# n64_4_port.net
KiCad netlist of a schematic drawn in EAGLE
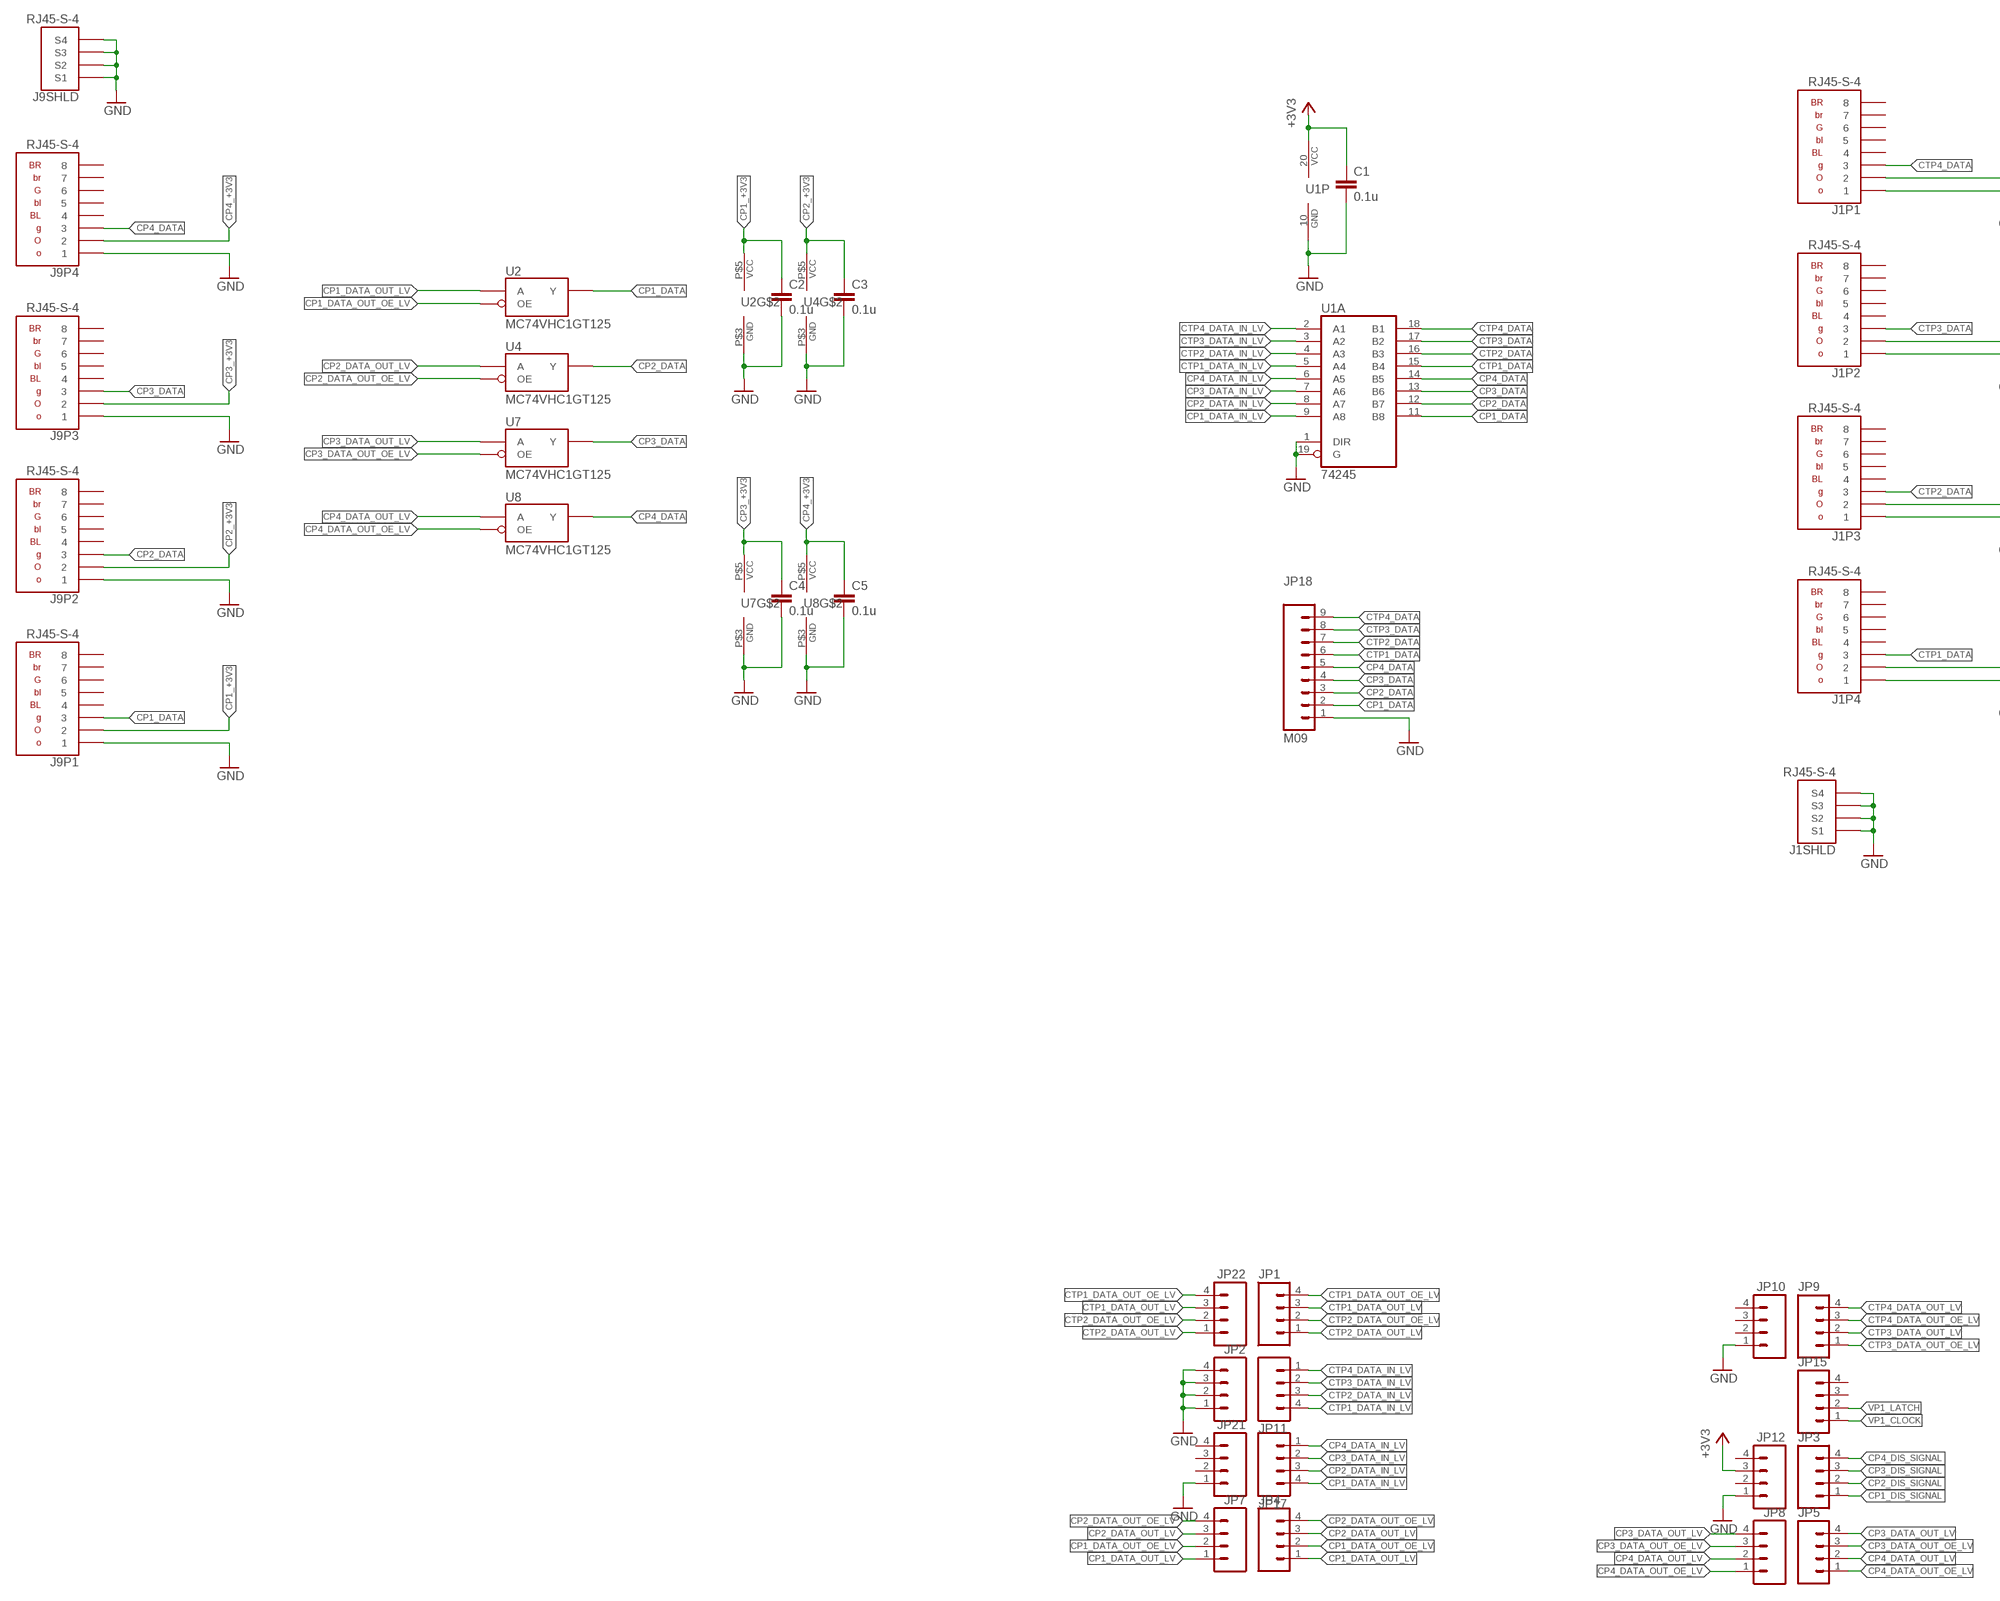
[diagram p0: schematic, sheet 1, part 1 of 2]
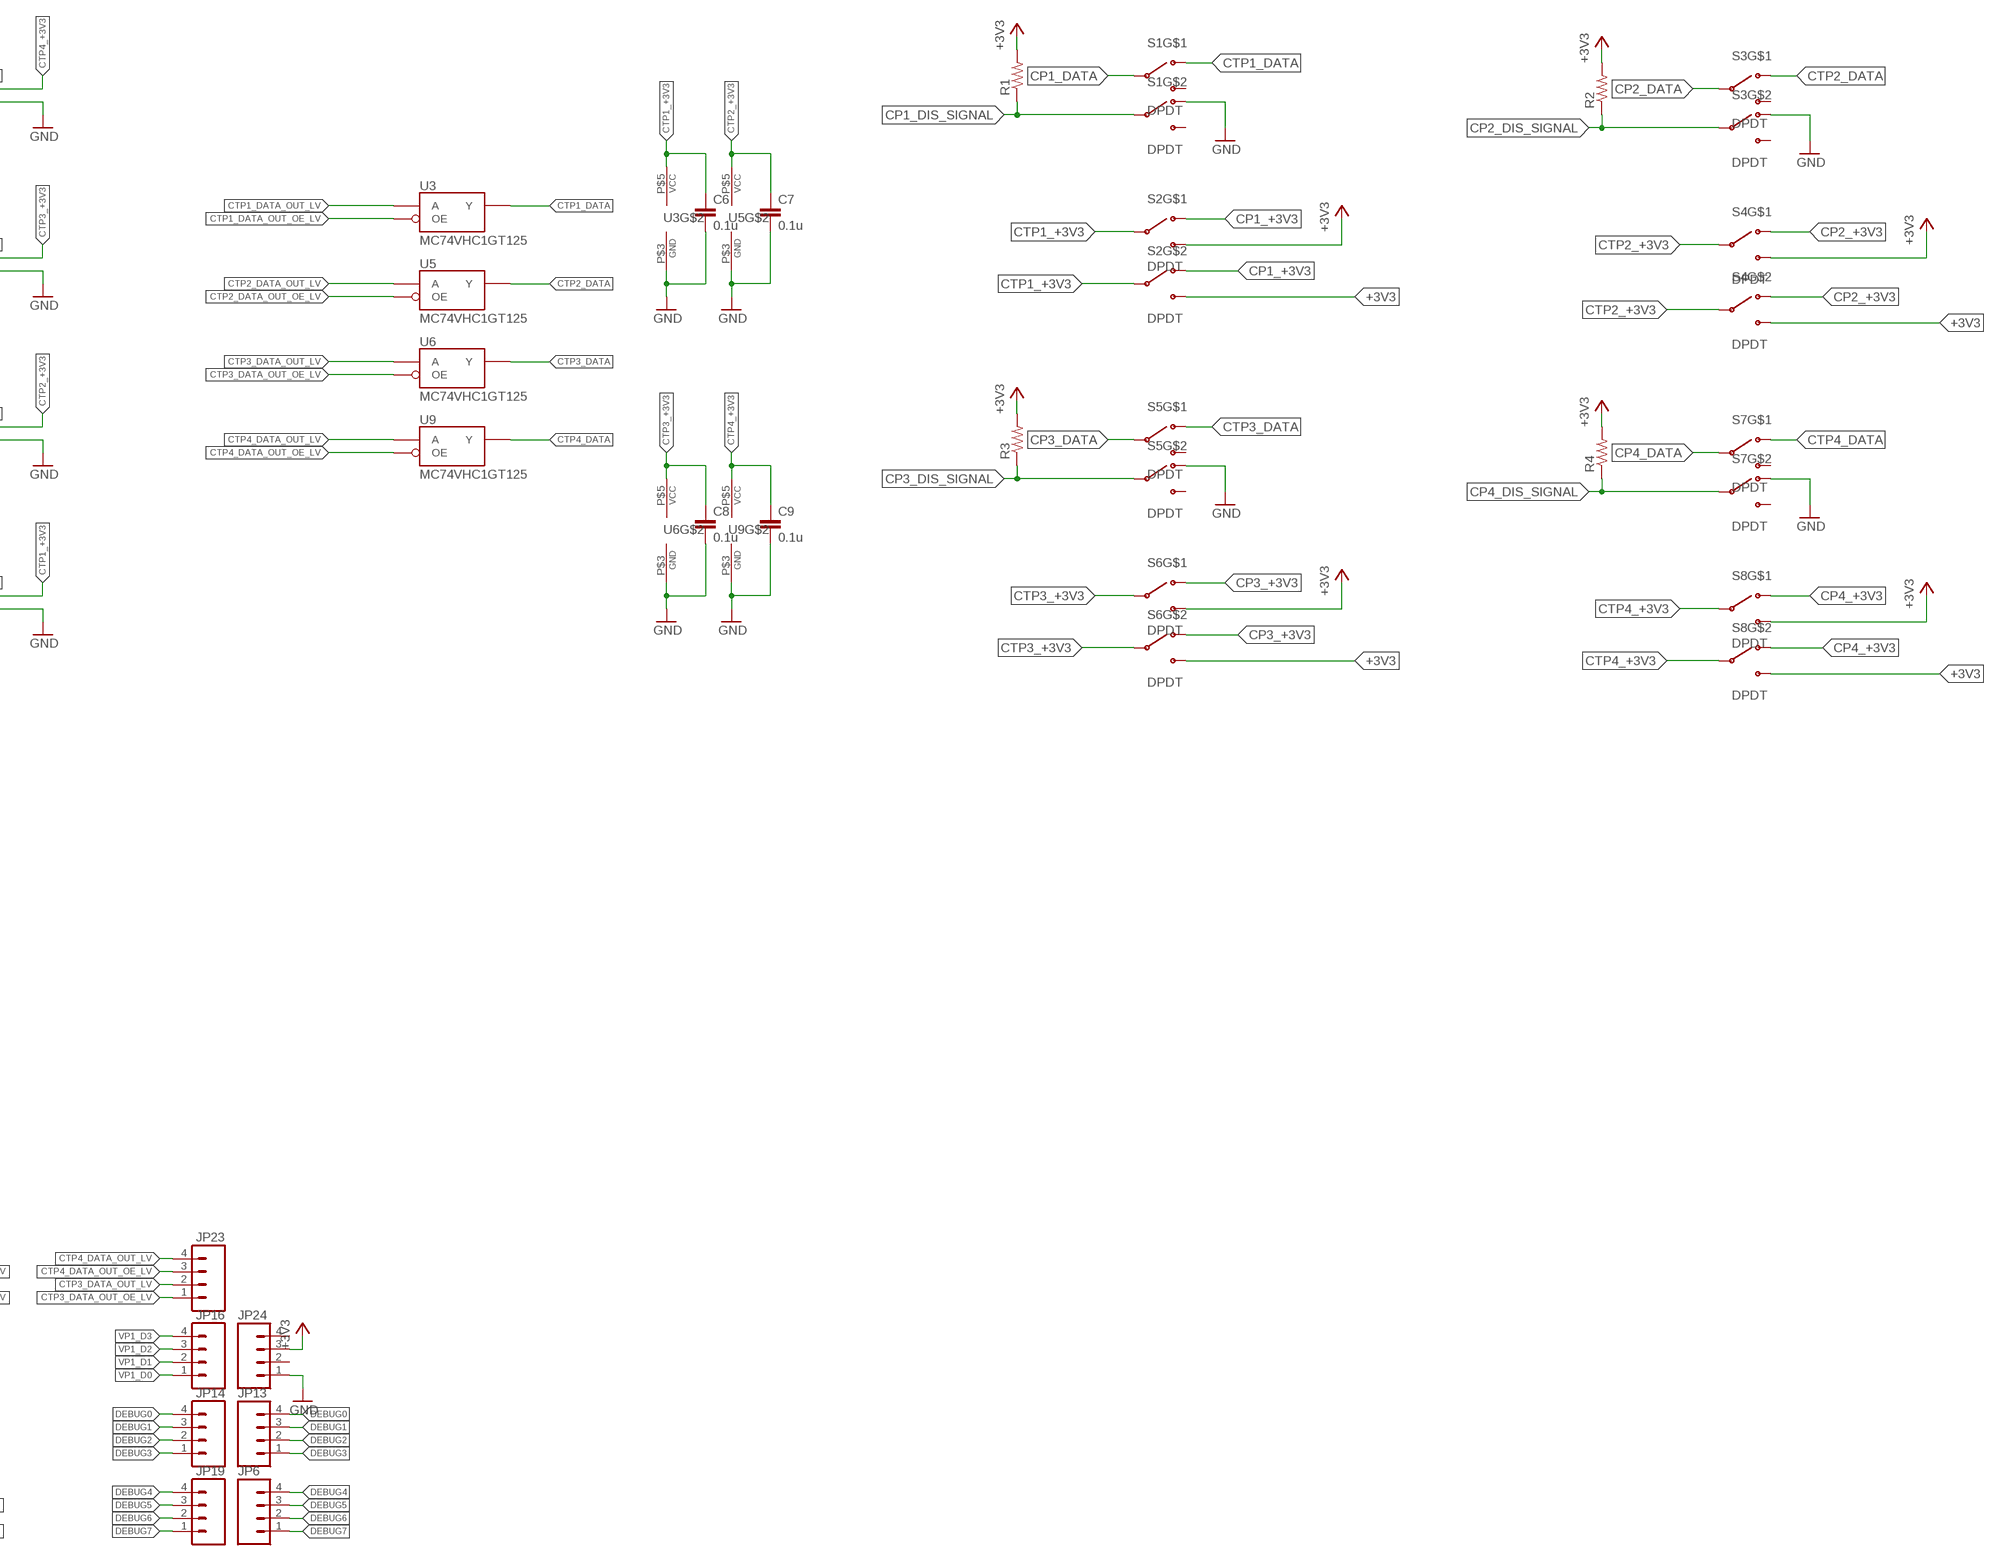
[diagram p1: schematic, sheet 1, part 2 of 2]

(export (version "E")
  (design (tool "Eeschema 10.0.6"))
  (components
    (comp (ref "C1")
      (value "0.1u")
      (footprint "eagle-import:C0603")
      (libsource (lib "eagle-import") (part "C-EUC0603"))
    )
    (comp (ref "C2")
      (value "0.1u")
      (footprint "eagle-import:C0603")
      (libsource (lib "eagle-import") (part "C-EUC0603"))
    )
    (comp (ref "C3")
      (value "0.1u")
      (footprint "eagle-import:C0603")
      (libsource (lib "eagle-import") (part "C-EUC0603"))
    )
    (comp (ref "C4")
      (value "0.1u")
      (footprint "eagle-import:C0603")
      (libsource (lib "eagle-import") (part "C-EUC0603"))
    )
    (comp (ref "C5")
      (value "0.1u")
      (footprint "eagle-import:C0603")
      (libsource (lib "eagle-import") (part "C-EUC0603"))
    )
    (comp (ref "C6")
      (value "0.1u")
      (footprint "eagle-import:C0603")
      (libsource (lib "eagle-import") (part "C-EUC0603"))
    )
    (comp (ref "C7")
      (value "0.1u")
      (footprint "eagle-import:C0603")
      (libsource (lib "eagle-import") (part "C-EUC0603"))
    )
    (comp (ref "C8")
      (value "0.1u")
      (footprint "eagle-import:C0603")
      (libsource (lib "eagle-import") (part "C-EUC0603"))
    )
    (comp (ref "C9")
      (value "0.1u")
      (footprint "eagle-import:C0603")
      (libsource (lib "eagle-import") (part "C-EUC0603"))
    )
    (comp (ref "J1")
      (value "RJ45-S-4")
      (footprint "eagle-import:RJ45-S-4")
      (libsource (lib "eagle-import") (part "RJ45-S-4"))
    )
    (comp (ref "J9")
      (value "RJ45-S-4")
      (footprint "eagle-import:RJ45-S-4")
      (libsource (lib "eagle-import") (part "RJ45-S-4"))
    )
    (comp (ref "JP1")
      (value "M04PTH")
      (footprint "eagle-import:1X04")
      (libsource (lib "eagle-import") (part "M04PTH"))
    )
    (comp (ref "JP2")
      (value "M04PTH")
      (footprint "eagle-import:1X04")
      (libsource (lib "eagle-import") (part "M04PTH"))
    )
    (comp (ref "JP3")
      (value "M04PTH")
      (footprint "eagle-import:1X04")
      (libsource (lib "eagle-import") (part "M04PTH"))
    )
    (comp (ref "JP4")
      (value "M04PTH")
      (footprint "eagle-import:1X04")
      (libsource (lib "eagle-import") (part "M04PTH"))
    )
    (comp (ref "JP5")
      (value "M04PTH")
      (footprint "eagle-import:1X04")
      (libsource (lib "eagle-import") (part "M04PTH"))
    )
    (comp (ref "JP6")
      (value "M04PTH")
      (footprint "eagle-import:1X04")
      (libsource (lib "eagle-import") (part "M04PTH"))
    )
    (comp (ref "JP7")
      (value "M04PTH")
      (footprint "eagle-import:1X04")
      (libsource (lib "eagle-import") (part "M04PTH"))
    )
    (comp (ref "JP8")
      (value "M04PTH")
      (footprint "eagle-import:1X04")
      (libsource (lib "eagle-import") (part "M04PTH"))
    )
    (comp (ref "JP9")
      (value "M04PTH")
      (footprint "eagle-import:1X04")
      (libsource (lib "eagle-import") (part "M04PTH"))
    )
    (comp (ref "JP10")
      (value "M04PTH")
      (footprint "eagle-import:1X04")
      (libsource (lib "eagle-import") (part "M04PTH"))
    )
    (comp (ref "JP11")
      (value "M04PTH")
      (footprint "eagle-import:1X04")
      (libsource (lib "eagle-import") (part "M04PTH"))
    )
    (comp (ref "JP12")
      (value "M04PTH")
      (footprint "eagle-import:1X04")
      (libsource (lib "eagle-import") (part "M04PTH"))
    )
    (comp (ref "JP13")
      (value "M04PTH")
      (footprint "eagle-import:1X04")
      (libsource (lib "eagle-import") (part "M04PTH"))
    )
    (comp (ref "JP14")
      (value "M04PTH")
      (footprint "eagle-import:1X04")
      (libsource (lib "eagle-import") (part "M04PTH"))
    )
    (comp (ref "JP15")
      (value "M04PTH")
      (footprint "eagle-import:1X04")
      (libsource (lib "eagle-import") (part "M04PTH"))
    )
    (comp (ref "JP16")
      (value "M04PTH")
      (footprint "eagle-import:1X04")
      (libsource (lib "eagle-import") (part "M04PTH"))
    )
    (comp (ref "JP17")
      (value "M04PTH")
      (footprint "eagle-import:1X04")
      (libsource (lib "eagle-import") (part "M04PTH"))
    )
    (comp (ref "JP18")
      (value "M09")
      (footprint "eagle-import:1X09")
      (libsource (lib "eagle-import") (part "M09"))
    )
    (comp (ref "JP19")
      (value "M04PTH")
      (footprint "eagle-import:1X04")
      (libsource (lib "eagle-import") (part "M04PTH"))
    )
    (comp (ref "JP21")
      (value "M04PTH")
      (footprint "eagle-import:1X04")
      (libsource (lib "eagle-import") (part "M04PTH"))
    )
    (comp (ref "JP22")
      (value "M04PTH")
      (footprint "eagle-import:1X04")
      (libsource (lib "eagle-import") (part "M04PTH"))
    )
    (comp (ref "JP23")
      (value "M04PTH")
      (footprint "eagle-import:1X04")
      (libsource (lib "eagle-import") (part "M04PTH"))
    )
    (comp (ref "JP24")
      (value "M04PTH")
      (footprint "eagle-import:1X04")
      (libsource (lib "eagle-import") (part "M04PTH"))
    )
    (comp (ref "R1")
      (value "R-US_0207/2V")
      (footprint "eagle-import:0207_2V")
      (libsource (lib "eagle-import") (part "R-US_0207/2V"))
    )
    (comp (ref "R2")
      (value "R-US_0207/2V")
      (footprint "eagle-import:0207_2V")
      (libsource (lib "eagle-import") (part "R-US_0207/2V"))
    )
    (comp (ref "R3")
      (value "R-US_0207/2V")
      (footprint "eagle-import:0207_2V")
      (libsource (lib "eagle-import") (part "R-US_0207/2V"))
    )
    (comp (ref "R4")
      (value "R-US_0207/2V")
      (footprint "eagle-import:0207_2V")
      (libsource (lib "eagle-import") (part "R-US_0207/2V"))
    )
    (comp (ref "S1")
      (value "DPDT")
      (footprint "eagle-import:JS202011CQN")
      (libsource (lib "eagle-import") (part "DPDT"))
    )
    (comp (ref "S2")
      (value "DPDT")
      (footprint "eagle-import:JS202011CQN")
      (libsource (lib "eagle-import") (part "DPDT"))
    )
    (comp (ref "S3")
      (value "DPDT")
      (footprint "eagle-import:JS202011CQN")
      (libsource (lib "eagle-import") (part "DPDT"))
    )
    (comp (ref "S4")
      (value "DPDT")
      (footprint "eagle-import:JS202011CQN")
      (libsource (lib "eagle-import") (part "DPDT"))
    )
    (comp (ref "S5")
      (value "DPDT")
      (footprint "eagle-import:JS202011CQN")
      (libsource (lib "eagle-import") (part "DPDT"))
    )
    (comp (ref "S6")
      (value "DPDT")
      (footprint "eagle-import:JS202011CQN")
      (libsource (lib "eagle-import") (part "DPDT"))
    )
    (comp (ref "S7")
      (value "DPDT")
      (footprint "eagle-import:JS202011CQN")
      (libsource (lib "eagle-import") (part "DPDT"))
    )
    (comp (ref "S8")
      (value "DPDT")
      (footprint "eagle-import:JS202011CQN")
      (libsource (lib "eagle-import") (part "DPDT"))
    )
    (comp (ref "U1")
      (value "74245")
      (footprint "eagle-import:DIL20")
      (libsource (lib "eagle-import") (part "74245"))
    )
    (comp (ref "U2")
      (value "MC74VHC1GT125")
      (footprint "eagle-import:TSOP-5")
      (libsource (lib "eagle-import") (part "MC74VHC1GT125"))
    )
    (comp (ref "U3")
      (value "MC74VHC1GT125")
      (footprint "eagle-import:TSOP-5")
      (libsource (lib "eagle-import") (part "MC74VHC1GT125"))
    )
    (comp (ref "U4")
      (value "MC74VHC1GT125")
      (footprint "eagle-import:TSOP-5")
      (libsource (lib "eagle-import") (part "MC74VHC1GT125"))
    )
    (comp (ref "U5")
      (value "MC74VHC1GT125")
      (footprint "eagle-import:TSOP-5")
      (libsource (lib "eagle-import") (part "MC74VHC1GT125"))
    )
    (comp (ref "U6")
      (value "MC74VHC1GT125")
      (footprint "eagle-import:TSOP-5")
      (libsource (lib "eagle-import") (part "MC74VHC1GT125"))
    )
    (comp (ref "U7")
      (value "MC74VHC1GT125")
      (footprint "eagle-import:TSOP-5")
      (libsource (lib "eagle-import") (part "MC74VHC1GT125"))
    )
    (comp (ref "U8")
      (value "MC74VHC1GT125")
      (footprint "eagle-import:TSOP-5")
      (libsource (lib "eagle-import") (part "MC74VHC1GT125"))
    )
    (comp (ref "U9")
      (value "MC74VHC1GT125")
      (footprint "eagle-import:TSOP-5")
      (libsource (lib "eagle-import") (part "MC74VHC1GT125"))
    )
  )
  (nets
    (net (code "1") (name "+3V3") (class "Default")
      (node (ref "C1") (pin "1") (pinfunction "1_1") (pintype "passive"))
      (node (ref "JP12") (pin "3") (pinfunction "3_3") (pintype "passive"))
      (node (ref "JP24") (pin "3") (pinfunction "3_3") (pintype "passive"))
      (node (ref "R1") (pin "2") (pinfunction "2_2") (pintype "passive"))
      (node (ref "R2") (pin "2") (pinfunction "2_2") (pintype "passive"))
      (node (ref "R3") (pin "2") (pinfunction "2_2") (pintype "passive"))
      (node (ref "R4") (pin "2") (pinfunction "2_2") (pintype "passive"))
      (node (ref "S2") (pin "3") (pinfunction "3_3") (pintype "bidirectional"))
      (node (ref "S2") (pin "6") (pinfunction "3_6") (pintype "bidirectional"))
      (node (ref "S4") (pin "3") (pinfunction "3_3") (pintype "bidirectional"))
      (node (ref "S4") (pin "6") (pinfunction "3_6") (pintype "bidirectional"))
      (node (ref "S6") (pin "3") (pinfunction "3_3") (pintype "bidirectional"))
      (node (ref "S6") (pin "6") (pinfunction "3_6") (pintype "bidirectional"))
      (node (ref "S8") (pin "3") (pinfunction "3_3") (pintype "bidirectional"))
      (node (ref "S8") (pin "6") (pinfunction "3_6") (pintype "bidirectional"))
      (node (ref "U1") (pin "20") (pinfunction "VCC_20") (pintype "power_in"))
    )
    (net (code "2") (name "CP1_+3V3") (class "Default")
      (node (ref "C2") (pin "1") (pinfunction "1_1") (pintype "passive"))
      (node (ref "J9") (pin "1-2") (pinfunction "2_1-2") (pintype "bidirectional"))
      (node (ref "S2") (pin "1") (pinfunction "1_1") (pintype "bidirectional"))
      (node (ref "S2") (pin "4") (pinfunction "1_4") (pintype "bidirectional"))
      (node (ref "U2") (pin "P$5") (pinfunction "VCC_P$5") (pintype "power_in"))
    )
    (net (code "3") (name "CP1_DATA") (class "Default")
      (node (ref "J9") (pin "1-3") (pinfunction "3_1-3") (pintype "bidirectional"))
      (node (ref "JP18") (pin "2") (pinfunction "2_2") (pintype "passive"))
      (node (ref "S1") (pin "2") (pinfunction "2_2") (pintype "bidirectional"))
      (node (ref "U1") (pin "11") (pinfunction "B8_11") (pintype "bidirectional"))
      (node (ref "U2") (pin "P$4") (pinfunction "Y_P$4") (pintype "bidirectional"))
    )
    (net (code "4") (name "CP1_DATA_IN_LV") (class "Default")
      (node (ref "JP17") (pin "4") (pinfunction "4_4") (pintype "passive"))
      (node (ref "U1") (pin "9") (pinfunction "A8_9") (pintype "bidirectional"))
    )
    (net (code "5") (name "CP1_DATA_OUT_LV") (class "Default")
      (node (ref "JP4") (pin "1") (pinfunction "1_1") (pintype "passive"))
      (node (ref "JP7") (pin "1") (pinfunction "1_1") (pintype "passive"))
      (node (ref "U2") (pin "P$2") (pinfunction "A_P$2") (pintype "bidirectional"))
    )
    (net (code "6") (name "CP1_DATA_OUT_OE_LV") (class "Default")
      (node (ref "JP4") (pin "2") (pinfunction "2_2") (pintype "passive"))
      (node (ref "JP7") (pin "2") (pinfunction "2_2") (pintype "passive"))
      (node (ref "U2") (pin "P$1") (pinfunction "OE_P$1") (pintype "bidirectional"))
    )
    (net (code "7") (name "CP1_DIS_SIGNAL") (class "Default")
      (node (ref "JP3") (pin "1") (pinfunction "1_1") (pintype "passive"))
      (node (ref "R1") (pin "1") (pinfunction "1_1") (pintype "passive"))
      (node (ref "S1") (pin "5") (pinfunction "2_5") (pintype "bidirectional"))
    )
    (net (code "8") (name "CP2_+3V3") (class "Default")
      (node (ref "C3") (pin "1") (pinfunction "1_1") (pintype "passive"))
      (node (ref "J9") (pin "2-2") (pinfunction "2_2-2") (pintype "bidirectional"))
      (node (ref "S4") (pin "1") (pinfunction "1_1") (pintype "bidirectional"))
      (node (ref "S4") (pin "4") (pinfunction "1_4") (pintype "bidirectional"))
      (node (ref "U4") (pin "P$5") (pinfunction "VCC_P$5") (pintype "power_in"))
    )
    (net (code "9") (name "CP2_DATA") (class "Default")
      (node (ref "J9") (pin "2-3") (pinfunction "3_2-3") (pintype "bidirectional"))
      (node (ref "JP18") (pin "3") (pinfunction "3_3") (pintype "passive"))
      (node (ref "S3") (pin "2") (pinfunction "2_2") (pintype "bidirectional"))
      (node (ref "U1") (pin "12") (pinfunction "B7_12") (pintype "bidirectional"))
      (node (ref "U4") (pin "P$4") (pinfunction "Y_P$4") (pintype "bidirectional"))
    )
    (net (code "10") (name "CP2_DATA_IN_LV") (class "Default")
      (node (ref "JP17") (pin "3") (pinfunction "3_3") (pintype "passive"))
      (node (ref "U1") (pin "8") (pinfunction "A7_8") (pintype "bidirectional"))
    )
    (net (code "11") (name "CP2_DATA_OUT_LV") (class "Default")
      (node (ref "JP4") (pin "3") (pinfunction "3_3") (pintype "passive"))
      (node (ref "JP7") (pin "3") (pinfunction "3_3") (pintype "passive"))
      (node (ref "U4") (pin "P$2") (pinfunction "A_P$2") (pintype "bidirectional"))
    )
    (net (code "12") (name "CP2_DATA_OUT_OE_LV") (class "Default")
      (node (ref "JP4") (pin "4") (pinfunction "4_4") (pintype "passive"))
      (node (ref "JP7") (pin "4") (pinfunction "4_4") (pintype "passive"))
      (node (ref "U4") (pin "P$1") (pinfunction "OE_P$1") (pintype "bidirectional"))
    )
    (net (code "13") (name "CP2_DIS_SIGNAL") (class "Default")
      (node (ref "JP3") (pin "2") (pinfunction "2_2") (pintype "passive"))
      (node (ref "R2") (pin "1") (pinfunction "1_1") (pintype "passive"))
      (node (ref "S3") (pin "5") (pinfunction "2_5") (pintype "bidirectional"))
    )
    (net (code "14") (name "CP3_+3V3") (class "Default")
      (node (ref "C4") (pin "1") (pinfunction "1_1") (pintype "passive"))
      (node (ref "J9") (pin "3-2") (pinfunction "2_3-2") (pintype "bidirectional"))
      (node (ref "S6") (pin "1") (pinfunction "1_1") (pintype "bidirectional"))
      (node (ref "S6") (pin "4") (pinfunction "1_4") (pintype "bidirectional"))
      (node (ref "U7") (pin "P$5") (pinfunction "VCC_P$5") (pintype "power_in"))
    )
    (net (code "15") (name "CP3_DATA") (class "Default")
      (node (ref "J9") (pin "3-3") (pinfunction "3_3-3") (pintype "bidirectional"))
      (node (ref "JP18") (pin "4") (pinfunction "4_4") (pintype "passive"))
      (node (ref "S5") (pin "2") (pinfunction "2_2") (pintype "bidirectional"))
      (node (ref "U1") (pin "13") (pinfunction "B6_13") (pintype "bidirectional"))
      (node (ref "U7") (pin "P$4") (pinfunction "Y_P$4") (pintype "bidirectional"))
    )
    (net (code "16") (name "CP3_DATA_IN_LV") (class "Default")
      (node (ref "JP17") (pin "2") (pinfunction "2_2") (pintype "passive"))
      (node (ref "U1") (pin "7") (pinfunction "A6_7") (pintype "bidirectional"))
    )
    (net (code "17") (name "CP3_DATA_OUT_LV") (class "Default")
      (node (ref "JP5") (pin "4") (pinfunction "4_4") (pintype "passive"))
      (node (ref "JP8") (pin "4") (pinfunction "4_4") (pintype "passive"))
      (node (ref "U7") (pin "P$2") (pinfunction "A_P$2") (pintype "bidirectional"))
    )
    (net (code "18") (name "CP3_DATA_OUT_OE_LV") (class "Default")
      (node (ref "JP5") (pin "3") (pinfunction "3_3") (pintype "passive"))
      (node (ref "JP8") (pin "3") (pinfunction "3_3") (pintype "passive"))
      (node (ref "U7") (pin "P$1") (pinfunction "OE_P$1") (pintype "bidirectional"))
    )
    (net (code "19") (name "CP3_DIS_SIGNAL") (class "Default")
      (node (ref "JP3") (pin "3") (pinfunction "3_3") (pintype "passive"))
      (node (ref "R3") (pin "1") (pinfunction "1_1") (pintype "passive"))
      (node (ref "S5") (pin "5") (pinfunction "2_5") (pintype "bidirectional"))
    )
    (net (code "20") (name "CP4_+3V3") (class "Default")
      (node (ref "C5") (pin "1") (pinfunction "1_1") (pintype "passive"))
      (node (ref "J9") (pin "4-2") (pinfunction "2_4-2") (pintype "bidirectional"))
      (node (ref "S8") (pin "1") (pinfunction "1_1") (pintype "bidirectional"))
      (node (ref "S8") (pin "4") (pinfunction "1_4") (pintype "bidirectional"))
      (node (ref "U8") (pin "P$5") (pinfunction "VCC_P$5") (pintype "power_in"))
    )
    (net (code "21") (name "CP4_DATA") (class "Default")
      (node (ref "J9") (pin "4-3") (pinfunction "3_4-3") (pintype "bidirectional"))
      (node (ref "JP18") (pin "5") (pinfunction "5_5") (pintype "passive"))
      (node (ref "S7") (pin "2") (pinfunction "2_2") (pintype "bidirectional"))
      (node (ref "U1") (pin "14") (pinfunction "B5_14") (pintype "bidirectional"))
      (node (ref "U8") (pin "P$4") (pinfunction "Y_P$4") (pintype "bidirectional"))
    )
    (net (code "22") (name "CP4_DATA_IN_LV") (class "Default")
      (node (ref "JP17") (pin "1") (pinfunction "1_1") (pintype "passive"))
      (node (ref "U1") (pin "6") (pinfunction "A5_6") (pintype "bidirectional"))
    )
    (net (code "23") (name "CP4_DATA_OUT_LV") (class "Default")
      (node (ref "JP5") (pin "2") (pinfunction "2_2") (pintype "passive"))
      (node (ref "JP8") (pin "2") (pinfunction "2_2") (pintype "passive"))
      (node (ref "U8") (pin "P$2") (pinfunction "A_P$2") (pintype "bidirectional"))
    )
    (net (code "24") (name "CP4_DATA_OUT_OE_LV") (class "Default")
      (node (ref "JP5") (pin "1") (pinfunction "1_1") (pintype "passive"))
      (node (ref "JP8") (pin "1") (pinfunction "1_1") (pintype "passive"))
      (node (ref "U8") (pin "P$1") (pinfunction "OE_P$1") (pintype "bidirectional"))
    )
    (net (code "25") (name "CP4_DIS_SIGNAL") (class "Default")
      (node (ref "JP3") (pin "4") (pinfunction "4_4") (pintype "passive"))
      (node (ref "R4") (pin "1") (pinfunction "1_1") (pintype "passive"))
      (node (ref "S7") (pin "5") (pinfunction "2_5") (pintype "bidirectional"))
    )
    (net (code "26") (name "CTP1_+3V3") (class "Default")
      (node (ref "C6") (pin "1") (pinfunction "1_1") (pintype "passive"))
      (node (ref "J1") (pin "4-2") (pinfunction "2_4-2") (pintype "bidirectional"))
      (node (ref "S2") (pin "2") (pinfunction "2_2") (pintype "bidirectional"))
      (node (ref "S2") (pin "5") (pinfunction "2_5") (pintype "bidirectional"))
      (node (ref "U3") (pin "P$5") (pinfunction "VCC_P$5") (pintype "power_in"))
    )
    (net (code "27") (name "CTP1_DATA") (class "Default")
      (node (ref "J1") (pin "4-3") (pinfunction "3_4-3") (pintype "bidirectional"))
      (node (ref "JP18") (pin "6") (pinfunction "6_6") (pintype "passive"))
      (node (ref "S1") (pin "1") (pinfunction "1_1") (pintype "bidirectional"))
      (node (ref "U1") (pin "15") (pinfunction "B4_15") (pintype "bidirectional"))
      (node (ref "U3") (pin "P$4") (pinfunction "Y_P$4") (pintype "bidirectional"))
    )
    (net (code "28") (name "CTP1_DATA_IN_LV") (class "Default")
      (node (ref "JP11") (pin "4") (pinfunction "4_4") (pintype "passive"))
      (node (ref "U1") (pin "5") (pinfunction "A4_5") (pintype "bidirectional"))
    )
    (net (code "29") (name "CTP1_DATA_OUT_LV") (class "Default")
      (node (ref "JP1") (pin "3") (pinfunction "3_3") (pintype "passive"))
      (node (ref "JP22") (pin "3") (pinfunction "3_3") (pintype "passive"))
      (node (ref "U3") (pin "P$2") (pinfunction "A_P$2") (pintype "bidirectional"))
    )
    (net (code "30") (name "CTP1_DATA_OUT_OE_LV") (class "Default")
      (node (ref "JP1") (pin "4") (pinfunction "4_4") (pintype "passive"))
      (node (ref "JP22") (pin "4") (pinfunction "4_4") (pintype "passive"))
      (node (ref "U3") (pin "P$1") (pinfunction "OE_P$1") (pintype "bidirectional"))
    )
    (net (code "31") (name "CTP2_+3V3") (class "Default")
      (node (ref "C7") (pin "1") (pinfunction "1_1") (pintype "passive"))
      (node (ref "J1") (pin "3-2") (pinfunction "2_3-2") (pintype "bidirectional"))
      (node (ref "S4") (pin "2") (pinfunction "2_2") (pintype "bidirectional"))
      (node (ref "S4") (pin "5") (pinfunction "2_5") (pintype "bidirectional"))
      (node (ref "U5") (pin "P$5") (pinfunction "VCC_P$5") (pintype "power_in"))
    )
    (net (code "32") (name "CTP2_DATA") (class "Default")
      (node (ref "J1") (pin "3-3") (pinfunction "3_3-3") (pintype "bidirectional"))
      (node (ref "JP18") (pin "7") (pinfunction "7_7") (pintype "passive"))
      (node (ref "S3") (pin "1") (pinfunction "1_1") (pintype "bidirectional"))
      (node (ref "U1") (pin "16") (pinfunction "B3_16") (pintype "bidirectional"))
      (node (ref "U5") (pin "P$4") (pinfunction "Y_P$4") (pintype "bidirectional"))
    )
    (net (code "33") (name "CTP2_DATA_IN_LV") (class "Default")
      (node (ref "JP11") (pin "3") (pinfunction "3_3") (pintype "passive"))
      (node (ref "U1") (pin "4") (pinfunction "A3_4") (pintype "bidirectional"))
    )
    (net (code "34") (name "CTP2_DATA_OUT_LV") (class "Default")
      (node (ref "JP1") (pin "1") (pinfunction "1_1") (pintype "passive"))
      (node (ref "JP22") (pin "1") (pinfunction "1_1") (pintype "passive"))
      (node (ref "U5") (pin "P$2") (pinfunction "A_P$2") (pintype "bidirectional"))
    )
    (net (code "35") (name "CTP2_DATA_OUT_OE_LV") (class "Default")
      (node (ref "JP1") (pin "2") (pinfunction "2_2") (pintype "passive"))
      (node (ref "JP22") (pin "2") (pinfunction "2_2") (pintype "passive"))
      (node (ref "U5") (pin "P$1") (pinfunction "OE_P$1") (pintype "bidirectional"))
    )
    (net (code "36") (name "CTP3_+3V3") (class "Default")
      (node (ref "C8") (pin "1") (pinfunction "1_1") (pintype "passive"))
      (node (ref "J1") (pin "2-2") (pinfunction "2_2-2") (pintype "bidirectional"))
      (node (ref "S6") (pin "2") (pinfunction "2_2") (pintype "bidirectional"))
      (node (ref "S6") (pin "5") (pinfunction "2_5") (pintype "bidirectional"))
      (node (ref "U6") (pin "P$5") (pinfunction "VCC_P$5") (pintype "power_in"))
    )
    (net (code "37") (name "CTP3_DATA") (class "Default")
      (node (ref "J1") (pin "2-3") (pinfunction "3_2-3") (pintype "bidirectional"))
      (node (ref "JP18") (pin "8") (pinfunction "8_8") (pintype "passive"))
      (node (ref "S5") (pin "1") (pinfunction "1_1") (pintype "bidirectional"))
      (node (ref "U1") (pin "17") (pinfunction "B2_17") (pintype "bidirectional"))
      (node (ref "U6") (pin "P$4") (pinfunction "Y_P$4") (pintype "bidirectional"))
    )
    (net (code "38") (name "CTP3_DATA_IN_LV") (class "Default")
      (node (ref "JP11") (pin "2") (pinfunction "2_2") (pintype "passive"))
      (node (ref "U1") (pin "3") (pinfunction "A2_3") (pintype "bidirectional"))
    )
    (net (code "39") (name "CTP3_DATA_OUT_LV") (class "Default")
      (node (ref "JP23") (pin "2") (pinfunction "2_2") (pintype "passive"))
      (node (ref "JP9") (pin "2") (pinfunction "2_2") (pintype "passive"))
      (node (ref "U6") (pin "P$2") (pinfunction "A_P$2") (pintype "bidirectional"))
    )
    (net (code "40") (name "CTP3_DATA_OUT_OE_LV") (class "Default")
      (node (ref "JP23") (pin "1") (pinfunction "1_1") (pintype "passive"))
      (node (ref "JP9") (pin "1") (pinfunction "1_1") (pintype "passive"))
      (node (ref "U6") (pin "P$1") (pinfunction "OE_P$1") (pintype "bidirectional"))
    )
    (net (code "41") (name "CTP4_+3V3") (class "Default")
      (node (ref "C9") (pin "1") (pinfunction "1_1") (pintype "passive"))
      (node (ref "J1") (pin "1-2") (pinfunction "2_1-2") (pintype "bidirectional"))
      (node (ref "S8") (pin "2") (pinfunction "2_2") (pintype "bidirectional"))
      (node (ref "S8") (pin "5") (pinfunction "2_5") (pintype "bidirectional"))
      (node (ref "U9") (pin "P$5") (pinfunction "VCC_P$5") (pintype "power_in"))
    )
    (net (code "42") (name "CTP4_DATA") (class "Default")
      (node (ref "J1") (pin "1-3") (pinfunction "3_1-3") (pintype "bidirectional"))
      (node (ref "JP18") (pin "9") (pinfunction "9_9") (pintype "passive"))
      (node (ref "S7") (pin "1") (pinfunction "1_1") (pintype "bidirectional"))
      (node (ref "U1") (pin "18") (pinfunction "B1_18") (pintype "bidirectional"))
      (node (ref "U9") (pin "P$4") (pinfunction "Y_P$4") (pintype "bidirectional"))
    )
    (net (code "43") (name "CTP4_DATA_IN_LV") (class "Default")
      (node (ref "JP11") (pin "1") (pinfunction "1_1") (pintype "passive"))
      (node (ref "U1") (pin "2") (pinfunction "A1_2") (pintype "bidirectional"))
    )
    (net (code "44") (name "CTP4_DATA_OUT_LV") (class "Default")
      (node (ref "JP23") (pin "4") (pinfunction "4_4") (pintype "passive"))
      (node (ref "JP9") (pin "4") (pinfunction "4_4") (pintype "passive"))
      (node (ref "U9") (pin "P$2") (pinfunction "A_P$2") (pintype "bidirectional"))
    )
    (net (code "45") (name "CTP4_DATA_OUT_OE_LV") (class "Default")
      (node (ref "JP23") (pin "3") (pinfunction "3_3") (pintype "passive"))
      (node (ref "JP9") (pin "3") (pinfunction "3_3") (pintype "passive"))
      (node (ref "U9") (pin "P$1") (pinfunction "OE_P$1") (pintype "bidirectional"))
    )
    (net (code "46") (name "DEBUG0") (class "Default")
      (node (ref "JP13") (pin "4") (pinfunction "4_4") (pintype "passive"))
      (node (ref "JP14") (pin "4") (pinfunction "4_4") (pintype "passive"))
    )
    (net (code "47") (name "DEBUG1") (class "Default")
      (node (ref "JP13") (pin "3") (pinfunction "3_3") (pintype "passive"))
      (node (ref "JP14") (pin "3") (pinfunction "3_3") (pintype "passive"))
    )
    (net (code "48") (name "DEBUG2") (class "Default")
      (node (ref "JP13") (pin "2") (pinfunction "2_2") (pintype "passive"))
      (node (ref "JP14") (pin "2") (pinfunction "2_2") (pintype "passive"))
    )
    (net (code "49") (name "DEBUG3") (class "Default")
      (node (ref "JP13") (pin "1") (pinfunction "1_1") (pintype "passive"))
      (node (ref "JP14") (pin "1") (pinfunction "1_1") (pintype "passive"))
    )
    (net (code "50") (name "DEBUG4") (class "Default")
      (node (ref "JP19") (pin "4") (pinfunction "4_4") (pintype "passive"))
      (node (ref "JP6") (pin "4") (pinfunction "4_4") (pintype "passive"))
    )
    (net (code "51") (name "DEBUG5") (class "Default")
      (node (ref "JP19") (pin "3") (pinfunction "3_3") (pintype "passive"))
      (node (ref "JP6") (pin "3") (pinfunction "3_3") (pintype "passive"))
    )
    (net (code "52") (name "DEBUG6") (class "Default")
      (node (ref "JP19") (pin "2") (pinfunction "2_2") (pintype "passive"))
      (node (ref "JP6") (pin "2") (pinfunction "2_2") (pintype "passive"))
    )
    (net (code "53") (name "DEBUG7") (class "Default")
      (node (ref "JP19") (pin "1") (pinfunction "1_1") (pintype "passive"))
      (node (ref "JP6") (pin "1") (pinfunction "1_1") (pintype "passive"))
    )
    (net (code "54") (name "GND") (class "Default")
      (node (ref "C1") (pin "2") (pinfunction "2_2") (pintype "passive"))
      (node (ref "C2") (pin "2") (pinfunction "2_2") (pintype "passive"))
      (node (ref "C3") (pin "2") (pinfunction "2_2") (pintype "passive"))
      (node (ref "C4") (pin "2") (pinfunction "2_2") (pintype "passive"))
      (node (ref "C5") (pin "2") (pinfunction "2_2") (pintype "passive"))
      (node (ref "C6") (pin "2") (pinfunction "2_2") (pintype "passive"))
      (node (ref "C7") (pin "2") (pinfunction "2_2") (pintype "passive"))
      (node (ref "C8") (pin "2") (pinfunction "2_2") (pintype "passive"))
      (node (ref "C9") (pin "2") (pinfunction "2_2") (pintype "passive"))
      (node (ref "J1") (pin "1-1") (pinfunction "1_1-1") (pintype "bidirectional"))
      (node (ref "J1") (pin "2-1") (pinfunction "1_2-1") (pintype "bidirectional"))
      (node (ref "J1") (pin "3-1") (pinfunction "1_3-1") (pintype "bidirectional"))
      (node (ref "J1") (pin "4-1") (pinfunction "1_4-1") (pintype "bidirectional"))
      (node (ref "J1") (pin "S1") (pinfunction "S1_S1") (pintype "bidirectional"))
      (node (ref "J1") (pin "S2") (pinfunction "S2_S2") (pintype "bidirectional"))
      (node (ref "J1") (pin "S3") (pinfunction "S3_S3") (pintype "bidirectional"))
      (node (ref "J1") (pin "S4") (pinfunction "S4_S4") (pintype "bidirectional"))
      (node (ref "J9") (pin "1-1") (pinfunction "1_1-1") (pintype "bidirectional"))
      (node (ref "J9") (pin "2-1") (pinfunction "1_2-1") (pintype "bidirectional"))
      (node (ref "J9") (pin "3-1") (pinfunction "1_3-1") (pintype "bidirectional"))
      (node (ref "J9") (pin "4-1") (pinfunction "1_4-1") (pintype "bidirectional"))
      (node (ref "J9") (pin "S1") (pinfunction "S1_S1") (pintype "bidirectional"))
      (node (ref "J9") (pin "S2") (pinfunction "S2_S2") (pintype "bidirectional"))
      (node (ref "J9") (pin "S3") (pinfunction "S3_S3") (pintype "bidirectional"))
      (node (ref "J9") (pin "S4") (pinfunction "S4_S4") (pintype "bidirectional"))
      (node (ref "JP10") (pin "1") (pinfunction "1_1") (pintype "passive"))
      (node (ref "JP12") (pin "1") (pinfunction "1_1") (pintype "passive"))
      (node (ref "JP18") (pin "1") (pinfunction "1_1") (pintype "passive"))
      (node (ref "JP2") (pin "1") (pinfunction "1_1") (pintype "passive"))
      (node (ref "JP2") (pin "2") (pinfunction "2_2") (pintype "passive"))
      (node (ref "JP2") (pin "3") (pinfunction "3_3") (pintype "passive"))
      (node (ref "JP2") (pin "4") (pinfunction "4_4") (pintype "passive"))
      (node (ref "JP21") (pin "1") (pinfunction "1_1") (pintype "passive"))
      (node (ref "JP24") (pin "1") (pinfunction "1_1") (pintype "passive"))
      (node (ref "S1") (pin "4") (pinfunction "1_4") (pintype "bidirectional"))
      (node (ref "S3") (pin "4") (pinfunction "1_4") (pintype "bidirectional"))
      (node (ref "S5") (pin "4") (pinfunction "1_4") (pintype "bidirectional"))
      (node (ref "S7") (pin "4") (pinfunction "1_4") (pintype "bidirectional"))
      (node (ref "U1") (pin "1") (pinfunction "DIR_1") (pintype "input"))
      (node (ref "U1") (pin "10") (pinfunction "GND_10") (pintype "power_in"))
      (node (ref "U1") (pin "19") (pinfunction "G_19") (pintype "input"))
      (node (ref "U2") (pin "P$3") (pinfunction "GND_P$3") (pintype "power_in"))
      (node (ref "U3") (pin "P$3") (pinfunction "GND_P$3") (pintype "power_in"))
      (node (ref "U4") (pin "P$3") (pinfunction "GND_P$3") (pintype "power_in"))
      (node (ref "U5") (pin "P$3") (pinfunction "GND_P$3") (pintype "power_in"))
      (node (ref "U6") (pin "P$3") (pinfunction "GND_P$3") (pintype "power_in"))
      (node (ref "U7") (pin "P$3") (pinfunction "GND_P$3") (pintype "power_in"))
      (node (ref "U8") (pin "P$3") (pinfunction "GND_P$3") (pintype "power_in"))
      (node (ref "U9") (pin "P$3") (pinfunction "GND_P$3") (pintype "power_in"))
    )
    (net (code "55") (name "VP1_CLOCK") (class "Default")
      (node (ref "JP15") (pin "1") (pinfunction "1_1") (pintype "passive"))
    )
    (net (code "56") (name "VP1_D0") (class "Default")
      (node (ref "JP16") (pin "1") (pinfunction "1_1") (pintype "passive"))
    )
    (net (code "57") (name "VP1_D1") (class "Default")
      (node (ref "JP16") (pin "2") (pinfunction "2_2") (pintype "passive"))
    )
    (net (code "58") (name "VP1_D2") (class "Default")
      (node (ref "JP16") (pin "3") (pinfunction "3_3") (pintype "passive"))
    )
    (net (code "59") (name "VP1_D3") (class "Default")
      (node (ref "JP16") (pin "4") (pinfunction "4_4") (pintype "passive"))
    )
    (net (code "60") (name "VP1_LATCH") (class "Default")
      (node (ref "JP15") (pin "2") (pinfunction "2_2") (pintype "passive"))
    )
    (net (code "61") (name "unconnected-(J1A-4-Pad1-4)") (class "Default")
      (node (ref "J1") (pin "1-4") (pinfunction "4_1-4") (pintype "bidirectional"))
    )
    (net (code "62") (name "unconnected-(J1A-5-Pad1-5)") (class "Default")
      (node (ref "J1") (pin "1-5") (pinfunction "5_1-5") (pintype "bidirectional"))
    )
    (net (code "63") (name "unconnected-(J1A-6-Pad1-6)") (class "Default")
      (node (ref "J1") (pin "1-6") (pinfunction "6_1-6") (pintype "bidirectional"))
    )
    (net (code "64") (name "unconnected-(J1A-7-Pad1-7)") (class "Default")
      (node (ref "J1") (pin "1-7") (pinfunction "7_1-7") (pintype "bidirectional"))
    )
    (net (code "65") (name "unconnected-(J1A-8-Pad1-8)") (class "Default")
      (node (ref "J1") (pin "1-8") (pinfunction "8_1-8") (pintype "bidirectional"))
    )
    (net (code "66") (name "unconnected-(J1B-4-Pad2-4)") (class "Default")
      (node (ref "J1") (pin "2-4") (pinfunction "4_2-4") (pintype "bidirectional"))
    )
    (net (code "67") (name "unconnected-(J1B-5-Pad2-5)") (class "Default")
      (node (ref "J1") (pin "2-5") (pinfunction "5_2-5") (pintype "bidirectional"))
    )
    (net (code "68") (name "unconnected-(J1B-6-Pad2-6)") (class "Default")
      (node (ref "J1") (pin "2-6") (pinfunction "6_2-6") (pintype "bidirectional"))
    )
    (net (code "69") (name "unconnected-(J1B-7-Pad2-7)") (class "Default")
      (node (ref "J1") (pin "2-7") (pinfunction "7_2-7") (pintype "bidirectional"))
    )
    (net (code "70") (name "unconnected-(J1B-8-Pad2-8)") (class "Default")
      (node (ref "J1") (pin "2-8") (pinfunction "8_2-8") (pintype "bidirectional"))
    )
    (net (code "71") (name "unconnected-(J1C-4-Pad3-4)") (class "Default")
      (node (ref "J1") (pin "3-4") (pinfunction "4_3-4") (pintype "bidirectional"))
    )
    (net (code "72") (name "unconnected-(J1C-5-Pad3-5)") (class "Default")
      (node (ref "J1") (pin "3-5") (pinfunction "5_3-5") (pintype "bidirectional"))
    )
    (net (code "73") (name "unconnected-(J1C-6-Pad3-6)") (class "Default")
      (node (ref "J1") (pin "3-6") (pinfunction "6_3-6") (pintype "bidirectional"))
    )
    (net (code "74") (name "unconnected-(J1C-7-Pad3-7)") (class "Default")
      (node (ref "J1") (pin "3-7") (pinfunction "7_3-7") (pintype "bidirectional"))
    )
    (net (code "75") (name "unconnected-(J1C-8-Pad3-8)") (class "Default")
      (node (ref "J1") (pin "3-8") (pinfunction "8_3-8") (pintype "bidirectional"))
    )
    (net (code "76") (name "unconnected-(J1D-4-Pad4-4)") (class "Default")
      (node (ref "J1") (pin "4-4") (pinfunction "4_4-4") (pintype "bidirectional"))
    )
    (net (code "77") (name "unconnected-(J1D-5-Pad4-5)") (class "Default")
      (node (ref "J1") (pin "4-5") (pinfunction "5_4-5") (pintype "bidirectional"))
    )
    (net (code "78") (name "unconnected-(J1D-6-Pad4-6)") (class "Default")
      (node (ref "J1") (pin "4-6") (pinfunction "6_4-6") (pintype "bidirectional"))
    )
    (net (code "79") (name "unconnected-(J1D-7-Pad4-7)") (class "Default")
      (node (ref "J1") (pin "4-7") (pinfunction "7_4-7") (pintype "bidirectional"))
    )
    (net (code "80") (name "unconnected-(J1D-8-Pad4-8)") (class "Default")
      (node (ref "J1") (pin "4-8") (pinfunction "8_4-8") (pintype "bidirectional"))
    )
    (net (code "81") (name "unconnected-(J9A-4-Pad1-4)") (class "Default")
      (node (ref "J9") (pin "1-4") (pinfunction "4_1-4") (pintype "bidirectional"))
    )
    (net (code "82") (name "unconnected-(J9A-5-Pad1-5)") (class "Default")
      (node (ref "J9") (pin "1-5") (pinfunction "5_1-5") (pintype "bidirectional"))
    )
    (net (code "83") (name "unconnected-(J9A-6-Pad1-6)") (class "Default")
      (node (ref "J9") (pin "1-6") (pinfunction "6_1-6") (pintype "bidirectional"))
    )
    (net (code "84") (name "unconnected-(J9A-7-Pad1-7)") (class "Default")
      (node (ref "J9") (pin "1-7") (pinfunction "7_1-7") (pintype "bidirectional"))
    )
    (net (code "85") (name "unconnected-(J9A-8-Pad1-8)") (class "Default")
      (node (ref "J9") (pin "1-8") (pinfunction "8_1-8") (pintype "bidirectional"))
    )
    (net (code "86") (name "unconnected-(J9B-4-Pad2-4)") (class "Default")
      (node (ref "J9") (pin "2-4") (pinfunction "4_2-4") (pintype "bidirectional"))
    )
    (net (code "87") (name "unconnected-(J9B-5-Pad2-5)") (class "Default")
      (node (ref "J9") (pin "2-5") (pinfunction "5_2-5") (pintype "bidirectional"))
    )
    (net (code "88") (name "unconnected-(J9B-6-Pad2-6)") (class "Default")
      (node (ref "J9") (pin "2-6") (pinfunction "6_2-6") (pintype "bidirectional"))
    )
    (net (code "89") (name "unconnected-(J9B-7-Pad2-7)") (class "Default")
      (node (ref "J9") (pin "2-7") (pinfunction "7_2-7") (pintype "bidirectional"))
    )
    (net (code "90") (name "unconnected-(J9B-8-Pad2-8)") (class "Default")
      (node (ref "J9") (pin "2-8") (pinfunction "8_2-8") (pintype "bidirectional"))
    )
    (net (code "91") (name "unconnected-(J9C-4-Pad3-4)") (class "Default")
      (node (ref "J9") (pin "3-4") (pinfunction "4_3-4") (pintype "bidirectional"))
    )
    (net (code "92") (name "unconnected-(J9C-5-Pad3-5)") (class "Default")
      (node (ref "J9") (pin "3-5") (pinfunction "5_3-5") (pintype "bidirectional"))
    )
    (net (code "93") (name "unconnected-(J9C-6-Pad3-6)") (class "Default")
      (node (ref "J9") (pin "3-6") (pinfunction "6_3-6") (pintype "bidirectional"))
    )
    (net (code "94") (name "unconnected-(J9C-7-Pad3-7)") (class "Default")
      (node (ref "J9") (pin "3-7") (pinfunction "7_3-7") (pintype "bidirectional"))
    )
    (net (code "95") (name "unconnected-(J9C-8-Pad3-8)") (class "Default")
      (node (ref "J9") (pin "3-8") (pinfunction "8_3-8") (pintype "bidirectional"))
    )
    (net (code "96") (name "unconnected-(J9D-4-Pad4-4)") (class "Default")
      (node (ref "J9") (pin "4-4") (pinfunction "4_4-4") (pintype "bidirectional"))
    )
    (net (code "97") (name "unconnected-(J9D-5-Pad4-5)") (class "Default")
      (node (ref "J9") (pin "4-5") (pinfunction "5_4-5") (pintype "bidirectional"))
    )
    (net (code "98") (name "unconnected-(J9D-6-Pad4-6)") (class "Default")
      (node (ref "J9") (pin "4-6") (pinfunction "6_4-6") (pintype "bidirectional"))
    )
    (net (code "99") (name "unconnected-(J9D-7-Pad4-7)") (class "Default")
      (node (ref "J9") (pin "4-7") (pinfunction "7_4-7") (pintype "bidirectional"))
    )
    (net (code "100") (name "unconnected-(J9D-8-Pad4-8)") (class "Default")
      (node (ref "J9") (pin "4-8") (pinfunction "8_4-8") (pintype "bidirectional"))
    )
    (net (code "101") (name "unconnected-(JP10-Pad2)") (class "Default")
      (node (ref "JP10") (pin "2") (pinfunction "2_2") (pintype "passive"))
    )
    (net (code "102") (name "unconnected-(JP10-Pad3)") (class "Default")
      (node (ref "JP10") (pin "3") (pinfunction "3_3") (pintype "passive"))
    )
    (net (code "103") (name "unconnected-(JP10-Pad4)") (class "Default")
      (node (ref "JP10") (pin "4") (pinfunction "4_4") (pintype "passive"))
    )
    (net (code "104") (name "unconnected-(JP12-Pad2)") (class "Default")
      (node (ref "JP12") (pin "2") (pinfunction "2_2") (pintype "passive"))
    )
    (net (code "105") (name "unconnected-(JP12-Pad4)") (class "Default")
      (node (ref "JP12") (pin "4") (pinfunction "4_4") (pintype "passive"))
    )
    (net (code "106") (name "unconnected-(JP15-Pad3)") (class "Default")
      (node (ref "JP15") (pin "3") (pinfunction "3_3") (pintype "passive"))
    )
    (net (code "107") (name "unconnected-(JP15-Pad4)") (class "Default")
      (node (ref "JP15") (pin "4") (pinfunction "4_4") (pintype "passive"))
    )
    (net (code "108") (name "unconnected-(JP21-Pad2)") (class "Default")
      (node (ref "JP21") (pin "2") (pinfunction "2_2") (pintype "passive"))
    )
    (net (code "109") (name "unconnected-(JP21-Pad3)") (class "Default")
      (node (ref "JP21") (pin "3") (pinfunction "3_3") (pintype "passive"))
    )
    (net (code "110") (name "unconnected-(JP21-Pad4)") (class "Default")
      (node (ref "JP21") (pin "4") (pinfunction "4_4") (pintype "passive"))
    )
    (net (code "111") (name "unconnected-(JP24-Pad2)") (class "Default")
      (node (ref "JP24") (pin "2") (pinfunction "2_2") (pintype "passive"))
    )
    (net (code "112") (name "unconnected-(JP24-Pad4)") (class "Default")
      (node (ref "JP24") (pin "4") (pinfunction "4_4") (pintype "passive"))
    )
    (net (code "113") (name "unconnected-(S1-Pad3)") (class "Default")
      (node (ref "S1") (pin "3") (pinfunction "3_3") (pintype "bidirectional"))
    )
    (net (code "114") (name "unconnected-(S1B-3-Pad6)") (class "Default")
      (node (ref "S1") (pin "6") (pinfunction "3_6") (pintype "bidirectional"))
    )
    (net (code "115") (name "unconnected-(S3-Pad3)") (class "Default")
      (node (ref "S3") (pin "3") (pinfunction "3_3") (pintype "bidirectional"))
    )
    (net (code "116") (name "unconnected-(S3B-3-Pad6)") (class "Default")
      (node (ref "S3") (pin "6") (pinfunction "3_6") (pintype "bidirectional"))
    )
    (net (code "117") (name "unconnected-(S5-Pad3)") (class "Default")
      (node (ref "S5") (pin "3") (pinfunction "3_3") (pintype "bidirectional"))
    )
    (net (code "118") (name "unconnected-(S5B-3-Pad6)") (class "Default")
      (node (ref "S5") (pin "6") (pinfunction "3_6") (pintype "bidirectional"))
    )
    (net (code "119") (name "unconnected-(S7-Pad3)") (class "Default")
      (node (ref "S7") (pin "3") (pinfunction "3_3") (pintype "bidirectional"))
    )
    (net (code "120") (name "unconnected-(S7B-3-Pad6)") (class "Default")
      (node (ref "S7") (pin "6") (pinfunction "3_6") (pintype "bidirectional"))
    )
  )
)
